# PowerMeterShield.net
KiCad netlist of a schematic drawn in EAGLE
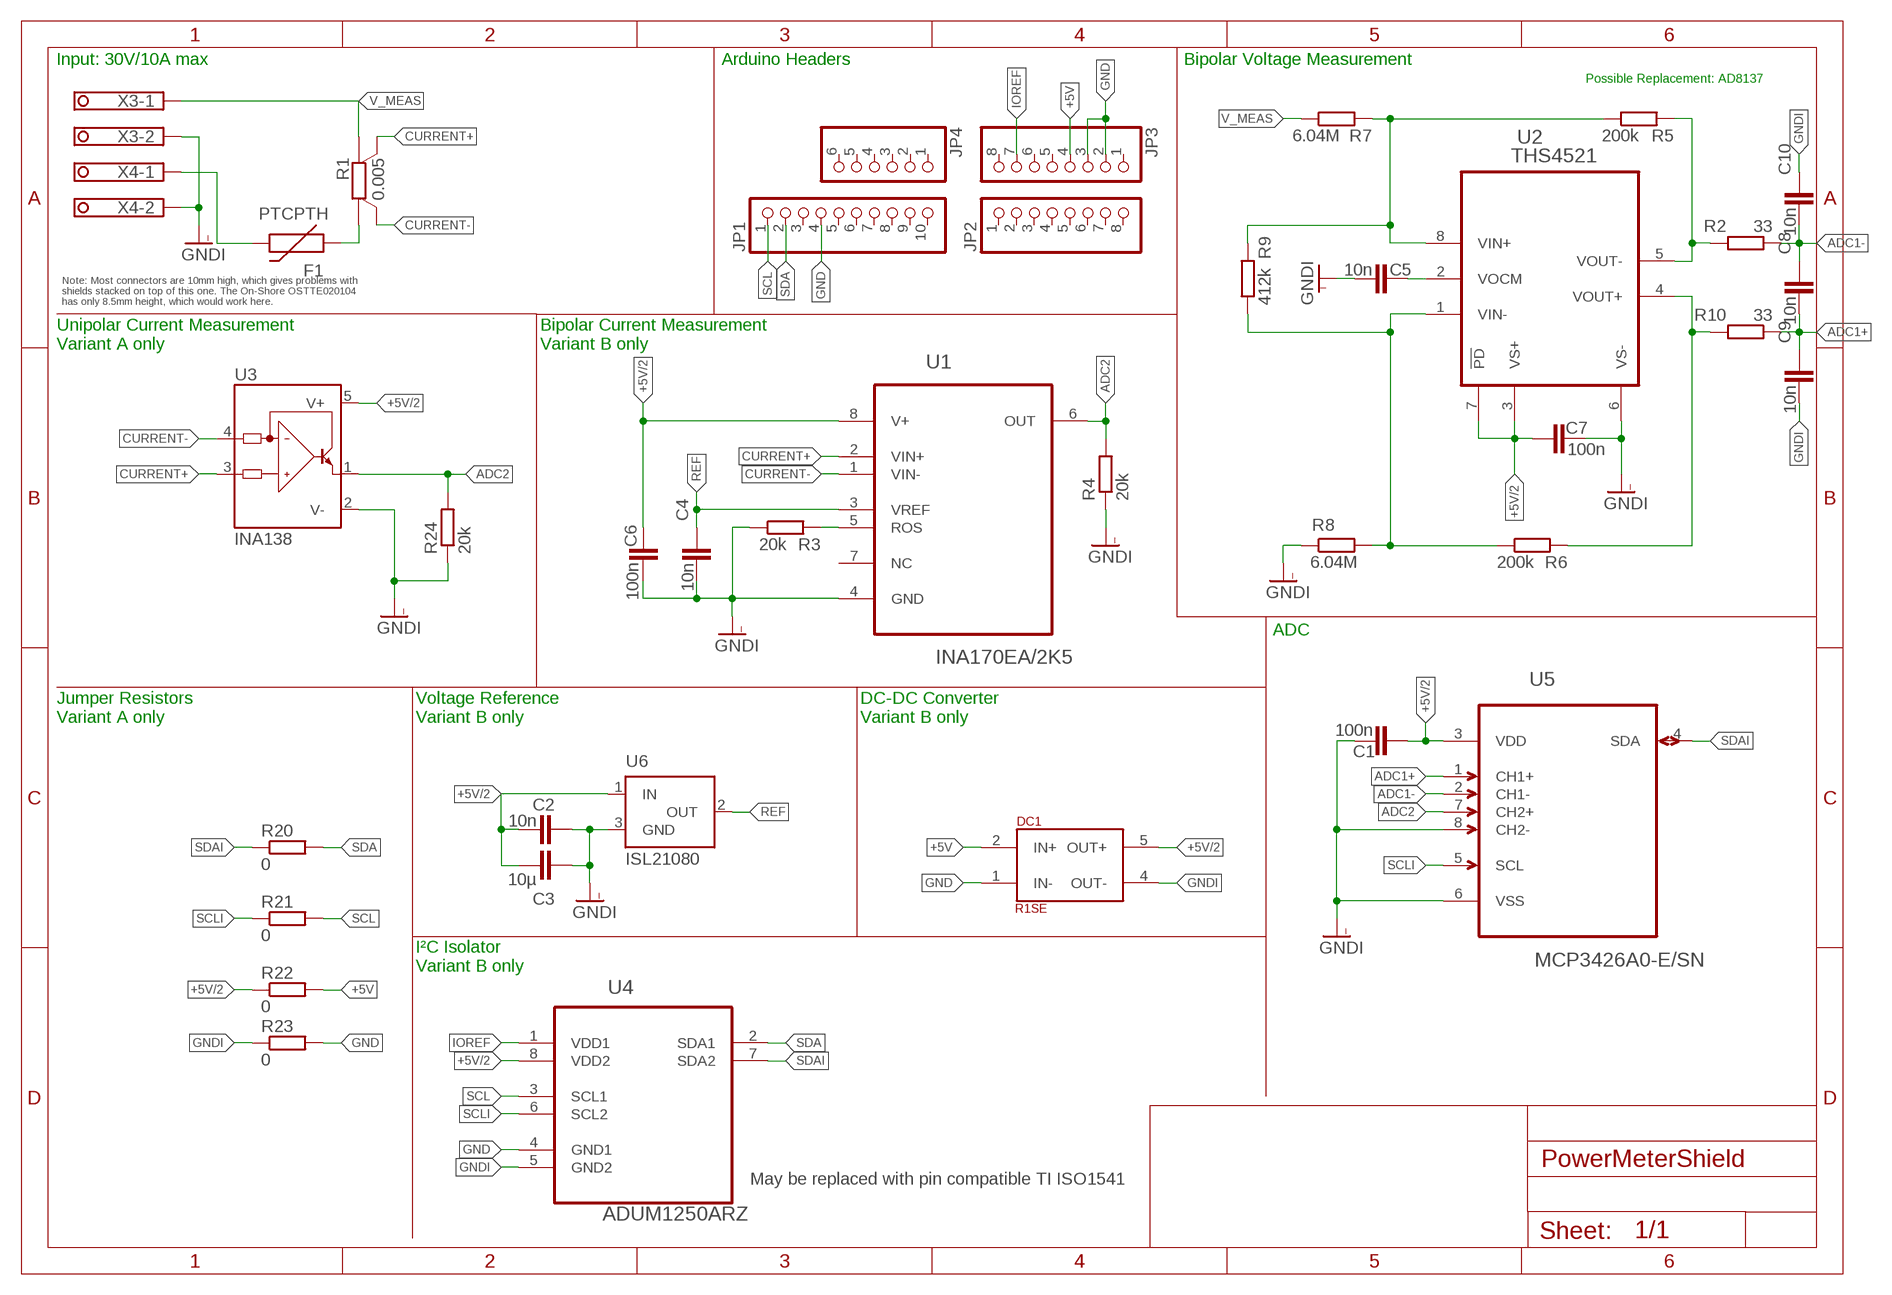
[diagram p0: schematic, sheet 1]

(export (version "E")
  (design (tool "Eeschema 10.0.6"))
  (components
    (comp (ref "C1")
      (value "100n")
      (footprint "eagle-import:C0805")
      (libsource (lib "eagle-import") (part "C-EUC0805"))
    )
    (comp (ref "C2")
      (value "10n")
      (footprint "eagle-import:C0805")
      (libsource (lib "eagle-import") (part "C-EUC0805"))
    )
    (comp (ref "C3")
      (value "10µ")
      (footprint "eagle-import:C0805")
      (libsource (lib "eagle-import") (part "C-EUC0805"))
    )
    (comp (ref "C4")
      (value "10n")
      (footprint "eagle-import:C0805")
      (libsource (lib "eagle-import") (part "C-EUC0805"))
    )
    (comp (ref "C5")
      (value "10n")
      (footprint "eagle-import:C0805")
      (libsource (lib "eagle-import") (part "C-EUC0805"))
    )
    (comp (ref "C6")
      (value "100n")
      (footprint "eagle-import:C0805")
      (libsource (lib "eagle-import") (part "C-EUC0805"))
    )
    (comp (ref "C7")
      (value "100n")
      (footprint "eagle-import:C0805")
      (libsource (lib "eagle-import") (part "C-EUC0805"))
    )
    (comp (ref "C8")
      (value "10n")
      (footprint "eagle-import:C0805")
      (libsource (lib "eagle-import") (part "C-EUC0805"))
    )
    (comp (ref "C9")
      (value "10n")
      (footprint "eagle-import:C0805")
      (libsource (lib "eagle-import") (part "C-EUC0805"))
    )
    (comp (ref "C10")
      (value "10n")
      (footprint "eagle-import:C0805")
      (libsource (lib "eagle-import") (part "C-EUC0805"))
    )
    (comp (ref "DC1")
      (value "R1SE")
      (footprint "eagle-import:R1SE")
      (libsource (lib "eagle-import") (part "R1SE"))
    )
    (comp (ref "F1")
      (value "PTCPTH")
      (footprint "eagle-import:PTC")
      (libsource (lib "eagle-import") (part "PTCPTH"))
    )
    (comp (ref "JP1")
      (value "PINHD-1X10")
      (footprint "eagle-import:1X10")
      (libsource (lib "eagle-import") (part "PINHD-1X10"))
    )
    (comp (ref "JP2")
      (value "PINHD-1X8")
      (footprint "eagle-import:1X08")
      (libsource (lib "eagle-import") (part "PINHD-1X8"))
    )
    (comp (ref "JP3")
      (value "PINHD-1X8")
      (footprint "eagle-import:1X08")
      (libsource (lib "eagle-import") (part "PINHD-1X8"))
    )
    (comp (ref "JP4")
      (value "PINHD-1X6")
      (footprint "eagle-import:1X06")
      (libsource (lib "eagle-import") (part "PINHD-1X6"))
    )
    (comp (ref "R1")
      (value "0.005")
      (footprint "eagle-import:CSM3637M")
      (libsource (lib "eagle-import") (part "SHUNT-4CSM3675M"))
    )
    (comp (ref "R2")
      (value "33")
      (footprint "eagle-import:R0805")
      (libsource (lib "eagle-import") (part "R-EU_R0805"))
    )
    (comp (ref "R3")
      (value "20k")
      (footprint "eagle-import:R0805")
      (libsource (lib "eagle-import") (part "R-EU_R0805"))
    )
    (comp (ref "R4")
      (value "20k")
      (footprint "eagle-import:R0805")
      (libsource (lib "eagle-import") (part "R-EU_R0805"))
    )
    (comp (ref "R5")
      (value "200k")
      (footprint "eagle-import:R0805")
      (libsource (lib "eagle-import") (part "R-EU_R0805"))
    )
    (comp (ref "R6")
      (value "200k")
      (footprint "eagle-import:R0805")
      (libsource (lib "eagle-import") (part "R-EU_R0805"))
    )
    (comp (ref "R7")
      (value "6.04M")
      (footprint "eagle-import:R0805")
      (libsource (lib "eagle-import") (part "R-EU_R0805"))
    )
    (comp (ref "R8")
      (value "6.04M")
      (footprint "eagle-import:R0805")
      (libsource (lib "eagle-import") (part "R-EU_R0805"))
    )
    (comp (ref "R9")
      (value "412k")
      (footprint "eagle-import:R0805")
      (libsource (lib "eagle-import") (part "R-EU_R0805"))
    )
    (comp (ref "R10")
      (value "33")
      (footprint "eagle-import:R0805")
      (libsource (lib "eagle-import") (part "R-EU_R0805"))
    )
    (comp (ref "R20")
      (value "0")
      (footprint "eagle-import:R2010")
      (libsource (lib "eagle-import") (part "R-EU_R2010"))
    )
    (comp (ref "R21")
      (value "0")
      (footprint "eagle-import:R2010")
      (libsource (lib "eagle-import") (part "R-EU_R2010"))
    )
    (comp (ref "R22")
      (value "0")
      (footprint "eagle-import:R2010")
      (libsource (lib "eagle-import") (part "R-EU_R2010"))
    )
    (comp (ref "R23")
      (value "0")
      (footprint "eagle-import:R2010")
      (libsource (lib "eagle-import") (part "R-EU_R2010"))
    )
    (comp (ref "R24")
      (value "20k")
      (footprint "eagle-import:R0805")
      (libsource (lib "eagle-import") (part "R-EU_R0805"))
    )
    (comp (ref "U1")
      (value "INA170EA/2K5")
      (footprint "eagle-import:SOP65P490X110-8N")
      (fields (field (name "OC_FARNELL") "1234851"))
      (libsource (lib "eagle-import") (part "INA170EA/2K5"))
    )
    (comp (ref "U2")
      (value "THS4521")
      (footprint "eagle-import:SOIC127P600X175-8N")
      (fields (field (name "MPN") "THS4531AID") (field (name "OC_FARNELL") "1755708"))
      (libsource (lib "eagle-import") (part "THS4531AID"))
    )
    (comp (ref "U3")
      (value "INA138")
      (footprint "eagle-import:SOT23-5")
      (fields (field (name "MF") "TEXAS INSTRUMENTS") (field (name "MPN") "INA138NA/250"))
      (libsource (lib "eagle-import") (part "INA138"))
    )
    (comp (ref "U4")
      (value "ADUM1250ARZ")
      (footprint "eagle-import:SOIC127P600X175-8N")
      (libsource (lib "eagle-import") (part "ADUM1250ARZ"))
    )
    (comp (ref "U5")
      (value "MCP3426A0-E/SN")
      (footprint "eagle-import:SOIC127P600X175-8N")
      (libsource (lib "eagle-import") (part "MCP3426A0-E/SN"))
    )
    (comp (ref "U6")
      (value "ISL21080")
      (footprint "eagle-import:SOT23")
      (fields (field (name "MF") "MAXIM") (field (name "MPN") "MAX6520EUR-T"))
      (libsource (lib "eagle-import") (part "MAX6520"))
    )
    (comp (ref "X3")
      (value "1751248")
      (footprint "eagle-import:1751248")
      (fields
        (field (name "OC_DIGIKEY") "ED2740-ND")
        (field (name "PRICE_10") "0.27")
        (field (name "PRICE_100") "0.19")
      )
      (libsource (lib "eagle-import") (part "1751248"))
    )
    (comp (ref "X4")
      (value "1751248")
      (footprint "eagle-import:1751248")
      (fields
        (field (name "OC_DIGIKEY") "ED2740-ND")
        (field (name "PRICE_10") "0.27")
        (field (name "PRICE_100") "0.19")
      )
      (libsource (lib "eagle-import") (part "1751248"))
    )
  )
  (nets
    (net (code "1") (name "+5V") (class "Default")
      (node (ref "DC1") (pin "2") (pinfunction "IN+_2") (pintype "bidirectional"))
      (node (ref "JP3") (pin "4") (pinfunction "4_4") (pintype "passive"))
      (node (ref "R22") (pin "2") (pinfunction "2_2") (pintype "passive"))
    )
    (net (code "2") (name "+5V{slash}2") (class "Default")
      (node (ref "C1") (pin "1") (pinfunction "1_1") (pintype "passive"))
      (node (ref "C2") (pin "1") (pinfunction "1_1") (pintype "passive"))
      (node (ref "C3") (pin "1") (pinfunction "1_1") (pintype "passive"))
      (node (ref "C6") (pin "1") (pinfunction "1_1") (pintype "passive"))
      (node (ref "C7") (pin "1") (pinfunction "1_1") (pintype "passive"))
      (node (ref "DC1") (pin "5") (pinfunction "OUT+_5") (pintype "bidirectional"))
      (node (ref "R22") (pin "1") (pinfunction "1_1") (pintype "passive"))
      (node (ref "U1") (pin "8") (pinfunction "V+_8") (pintype "power_in"))
      (node (ref "U2") (pin "3") (pinfunction "VS+_3") (pintype "input"))
      (node (ref "U2") (pin "7") (pinfunction "~{PD}_7") (pintype "power_in"))
      (node (ref "U3") (pin "5") (pinfunction "V+_5") (pintype "power_in"))
      (node (ref "U4") (pin "8") (pinfunction "VDD2_8") (pintype "power_in"))
      (node (ref "U5") (pin "3") (pinfunction "VDD_3") (pintype "power_in"))
      (node (ref "U6") (pin "1") (pinfunction "IN_1") (pintype "input"))
    )
    (net (code "3") (name "ADC1+") (class "Default")
      (node (ref "C8") (pin "1") (pinfunction "1_1") (pintype "passive"))
      (node (ref "C9") (pin "2") (pinfunction "2_2") (pintype "passive"))
      (node (ref "R10") (pin "1") (pinfunction "1_1") (pintype "passive"))
      (node (ref "U5") (pin "1") (pinfunction "CH1+_1") (pintype "input"))
    )
    (net (code "4") (name "ADC1-") (class "Default")
      (node (ref "C10") (pin "1") (pinfunction "1_1") (pintype "passive"))
      (node (ref "C8") (pin "2") (pinfunction "2_2") (pintype "passive"))
      (node (ref "R2") (pin "1") (pinfunction "1_1") (pintype "passive"))
      (node (ref "U5") (pin "2") (pinfunction "CH1-_2") (pintype "input"))
    )
    (net (code "5") (name "ADC2") (class "Default")
      (node (ref "R24") (pin "2") (pinfunction "2_2") (pintype "passive"))
      (node (ref "R4") (pin "2") (pinfunction "2_2") (pintype "passive"))
      (node (ref "U1") (pin "6") (pinfunction "OUT_6") (pintype "output"))
      (node (ref "U3") (pin "1") (pinfunction "OUT_1") (pintype "output"))
      (node (ref "U5") (pin "7") (pinfunction "CH2+_7") (pintype "input"))
    )
    (net (code "6") (name "CURRENT+") (class "Default")
      (node (ref "R1") (pin "S2") (pinfunction "S2_S2") (pintype "passive"))
      (node (ref "U1") (pin "2") (pinfunction "VIN+_2") (pintype "input"))
      (node (ref "U3") (pin "3") (pinfunction "IN+_3") (pintype "input"))
    )
    (net (code "7") (name "CURRENT-") (class "Default")
      (node (ref "R1") (pin "S1") (pinfunction "S1_S1") (pintype "passive"))
      (node (ref "U1") (pin "1") (pinfunction "VIN-_1") (pintype "input"))
      (node (ref "U3") (pin "4") (pinfunction "IN-_4") (pintype "input"))
    )
    (net (code "8") (name "GND") (class "Default")
      (node (ref "DC1") (pin "1") (pinfunction "IN-_1") (pintype "bidirectional"))
      (node (ref "JP1") (pin "4") (pinfunction "4_4") (pintype "passive"))
      (node (ref "JP3") (pin "2") (pinfunction "2_2") (pintype "passive"))
      (node (ref "JP3") (pin "3") (pinfunction "3_3") (pintype "passive"))
      (node (ref "R23") (pin "2") (pinfunction "2_2") (pintype "passive"))
      (node (ref "U4") (pin "4") (pinfunction "GND1_4") (pintype "passive"))
    )
    (net (code "9") (name "GNDI") (class "Default")
      (node (ref "C1") (pin "2") (pinfunction "2_2") (pintype "passive"))
      (node (ref "C10") (pin "2") (pinfunction "2_2") (pintype "passive"))
      (node (ref "C2") (pin "2") (pinfunction "2_2") (pintype "passive"))
      (node (ref "C3") (pin "2") (pinfunction "2_2") (pintype "passive"))
      (node (ref "C4") (pin "1") (pinfunction "1_1") (pintype "passive"))
      (node (ref "C5") (pin "1") (pinfunction "1_1") (pintype "passive"))
      (node (ref "C6") (pin "2") (pinfunction "2_2") (pintype "passive"))
      (node (ref "C7") (pin "2") (pinfunction "2_2") (pintype "passive"))
      (node (ref "C9") (pin "1") (pinfunction "1_1") (pintype "passive"))
      (node (ref "DC1") (pin "4") (pinfunction "OUT-_4") (pintype "bidirectional"))
      (node (ref "R23") (pin "1") (pinfunction "1_1") (pintype "passive"))
      (node (ref "R24") (pin "1") (pinfunction "1_1") (pintype "passive"))
      (node (ref "R3") (pin "1") (pinfunction "1_1") (pintype "passive"))
      (node (ref "R4") (pin "1") (pinfunction "1_1") (pintype "passive"))
      (node (ref "R8") (pin "1") (pinfunction "1_1") (pintype "passive"))
      (node (ref "U1") (pin "4") (pinfunction "GND_4") (pintype "passive"))
      (node (ref "U2") (pin "6") (pinfunction "VS-_6") (pintype "passive"))
      (node (ref "U3") (pin "2") (pinfunction "V-_2") (pintype "power_in"))
      (node (ref "U4") (pin "5") (pinfunction "GND2_5") (pintype "passive"))
      (node (ref "U5") (pin "6") (pinfunction "VSS_6") (pintype "power_in"))
      (node (ref "U5") (pin "8") (pinfunction "CH2-_8") (pintype "input"))
      (node (ref "U6") (pin "3") (pinfunction "GND_3") (pintype "power_in"))
      (node (ref "X3") (pin "2") (pinfunction "K_2") (pintype "passive"))
      (node (ref "X4") (pin "2") (pinfunction "K_2") (pintype "passive"))
    )
    (net (code "10") (name "IOREF") (class "Default")
      (node (ref "JP3") (pin "7") (pinfunction "7_7") (pintype "passive"))
      (node (ref "U4") (pin "1") (pinfunction "VDD1_1") (pintype "power_in"))
    )
    (net (code "11") (name "Net-(F1-1)") (class "Default")
      (node (ref "F1") (pin "P$1") (pinfunction "1_P$1") (pintype "bidirectional"))
      (node (ref "R1") (pin "I1") (pinfunction "I1_I1") (pintype "passive"))
    )
    (net (code "12") (name "Net-(F1-2)") (class "Default")
      (node (ref "F1") (pin "P$2") (pinfunction "2_P$2") (pintype "bidirectional"))
      (node (ref "X4") (pin "1") (pinfunction "K_1") (pintype "passive"))
    )
    (net (code "13") (name "Net-(U1-ROS)") (class "Default")
      (node (ref "R3") (pin "2") (pinfunction "2_2") (pintype "passive"))
      (node (ref "U1") (pin "5") (pinfunction "ROS_5") (pintype "input"))
    )
    (net (code "14") (name "Net-(U2-VIN+)") (class "Default")
      (node (ref "R5") (pin "1") (pinfunction "1_1") (pintype "passive"))
      (node (ref "R7") (pin "2") (pinfunction "2_2") (pintype "passive"))
      (node (ref "R9") (pin "2") (pinfunction "2_2") (pintype "passive"))
      (node (ref "U2") (pin "8") (pinfunction "VIN+_8") (pintype "input"))
    )
    (net (code "15") (name "Net-(U2-VIN-)") (class "Default")
      (node (ref "R6") (pin "1") (pinfunction "1_1") (pintype "passive"))
      (node (ref "R8") (pin "2") (pinfunction "2_2") (pintype "passive"))
      (node (ref "R9") (pin "1") (pinfunction "1_1") (pintype "passive"))
      (node (ref "U2") (pin "1") (pinfunction "VIN-_1") (pintype "passive"))
    )
    (net (code "16") (name "Net-(U2-VOCM)") (class "Default")
      (node (ref "C5") (pin "2") (pinfunction "2_2") (pintype "passive"))
      (node (ref "U2") (pin "2") (pinfunction "VOCM_2") (pintype "input"))
    )
    (net (code "17") (name "Net-(U2-VOUT+)") (class "Default")
      (node (ref "R10") (pin "2") (pinfunction "2_2") (pintype "passive"))
      (node (ref "R6") (pin "2") (pinfunction "2_2") (pintype "passive"))
      (node (ref "U2") (pin "4") (pinfunction "VOUT+_4") (pintype "output"))
    )
    (net (code "18") (name "Net-(U2-VOUT-)") (class "Default")
      (node (ref "R2") (pin "2") (pinfunction "2_2") (pintype "passive"))
      (node (ref "R5") (pin "2") (pinfunction "2_2") (pintype "passive"))
      (node (ref "U2") (pin "5") (pinfunction "VOUT-_5") (pintype "output"))
    )
    (net (code "19") (name "REF") (class "Default")
      (node (ref "C4") (pin "2") (pinfunction "2_2") (pintype "passive"))
      (node (ref "U1") (pin "3") (pinfunction "VREF_3") (pintype "input"))
      (node (ref "U6") (pin "2") (pinfunction "OUT_2") (pintype "output"))
    )
    (net (code "20") (name "SCL") (class "Default")
      (node (ref "JP1") (pin "1") (pinfunction "1_1") (pintype "passive"))
      (node (ref "R21") (pin "2") (pinfunction "2_2") (pintype "passive"))
      (node (ref "U4") (pin "3") (pinfunction "SCL1_3") (pintype "input"))
    )
    (net (code "21") (name "SCLI") (class "Default")
      (node (ref "R21") (pin "1") (pinfunction "1_1") (pintype "passive"))
      (node (ref "U4") (pin "6") (pinfunction "SCL2_6") (pintype "input"))
      (node (ref "U5") (pin "5") (pinfunction "SCL_5") (pintype "input"))
    )
    (net (code "22") (name "SDA") (class "Default")
      (node (ref "JP1") (pin "2") (pinfunction "2_2") (pintype "passive"))
      (node (ref "R20") (pin "2") (pinfunction "2_2") (pintype "passive"))
      (node (ref "U4") (pin "2") (pinfunction "SDA1_2") (pintype "bidirectional"))
    )
    (net (code "23") (name "SDAI") (class "Default")
      (node (ref "R20") (pin "1") (pinfunction "1_1") (pintype "passive"))
      (node (ref "U4") (pin "7") (pinfunction "SDA2_7") (pintype "bidirectional"))
      (node (ref "U5") (pin "4") (pinfunction "SDA_4") (pintype "bidirectional"))
    )
    (net (code "24") (name "V_MEAS") (class "Default")
      (node (ref "R1") (pin "I2") (pinfunction "I2_I2") (pintype "passive"))
      (node (ref "R7") (pin "1") (pinfunction "1_1") (pintype "passive"))
      (node (ref "X3") (pin "1") (pinfunction "K_1") (pintype "passive"))
    )
    (net (code "25") (name "unconnected-(JP1-Pad3)") (class "Default")
      (node (ref "JP1") (pin "3") (pinfunction "3_3") (pintype "passive"))
    )
    (net (code "26") (name "unconnected-(JP1-Pad5)") (class "Default")
      (node (ref "JP1") (pin "5") (pinfunction "5_5") (pintype "passive"))
    )
    (net (code "27") (name "unconnected-(JP1-Pad6)") (class "Default")
      (node (ref "JP1") (pin "6") (pinfunction "6_6") (pintype "passive"))
    )
    (net (code "28") (name "unconnected-(JP1-Pad7)") (class "Default")
      (node (ref "JP1") (pin "7") (pinfunction "7_7") (pintype "passive"))
    )
    (net (code "29") (name "unconnected-(JP1-Pad8)") (class "Default")
      (node (ref "JP1") (pin "8") (pinfunction "8_8") (pintype "passive"))
    )
    (net (code "30") (name "unconnected-(JP1-Pad9)") (class "Default")
      (node (ref "JP1") (pin "9") (pinfunction "9_9") (pintype "passive"))
    )
    (net (code "31") (name "unconnected-(JP1-Pad10)") (class "Default")
      (node (ref "JP1") (pin "10") (pinfunction "10_10") (pintype "passive"))
    )
    (net (code "32") (name "unconnected-(JP2-Pad1)") (class "Default")
      (node (ref "JP2") (pin "1") (pinfunction "1_1") (pintype "passive"))
    )
    (net (code "33") (name "unconnected-(JP2-Pad2)") (class "Default")
      (node (ref "JP2") (pin "2") (pinfunction "2_2") (pintype "passive"))
    )
    (net (code "34") (name "unconnected-(JP2-Pad3)") (class "Default")
      (node (ref "JP2") (pin "3") (pinfunction "3_3") (pintype "passive"))
    )
    (net (code "35") (name "unconnected-(JP2-Pad4)") (class "Default")
      (node (ref "JP2") (pin "4") (pinfunction "4_4") (pintype "passive"))
    )
    (net (code "36") (name "unconnected-(JP2-Pad5)") (class "Default")
      (node (ref "JP2") (pin "5") (pinfunction "5_5") (pintype "passive"))
    )
    (net (code "37") (name "unconnected-(JP2-Pad6)") (class "Default")
      (node (ref "JP2") (pin "6") (pinfunction "6_6") (pintype "passive"))
    )
    (net (code "38") (name "unconnected-(JP2-Pad7)") (class "Default")
      (node (ref "JP2") (pin "7") (pinfunction "7_7") (pintype "passive"))
    )
    (net (code "39") (name "unconnected-(JP2-Pad8)") (class "Default")
      (node (ref "JP2") (pin "8") (pinfunction "8_8") (pintype "passive"))
    )
    (net (code "40") (name "unconnected-(JP3-Pad1)") (class "Default")
      (node (ref "JP3") (pin "1") (pinfunction "1_1") (pintype "passive"))
    )
    (net (code "41") (name "unconnected-(JP3-Pad5)") (class "Default")
      (node (ref "JP3") (pin "5") (pinfunction "5_5") (pintype "passive"))
    )
    (net (code "42") (name "unconnected-(JP3-Pad6)") (class "Default")
      (node (ref "JP3") (pin "6") (pinfunction "6_6") (pintype "passive"))
    )
    (net (code "43") (name "unconnected-(JP3-Pad8)") (class "Default")
      (node (ref "JP3") (pin "8") (pinfunction "8_8") (pintype "passive"))
    )
    (net (code "44") (name "unconnected-(JP4-Pad1)") (class "Default")
      (node (ref "JP4") (pin "1") (pinfunction "1_1") (pintype "passive"))
    )
    (net (code "45") (name "unconnected-(JP4-Pad2)") (class "Default")
      (node (ref "JP4") (pin "2") (pinfunction "2_2") (pintype "passive"))
    )
    (net (code "46") (name "unconnected-(JP4-Pad3)") (class "Default")
      (node (ref "JP4") (pin "3") (pinfunction "3_3") (pintype "passive"))
    )
    (net (code "47") (name "unconnected-(JP4-Pad4)") (class "Default")
      (node (ref "JP4") (pin "4") (pinfunction "4_4") (pintype "passive"))
    )
    (net (code "48") (name "unconnected-(JP4-Pad5)") (class "Default")
      (node (ref "JP4") (pin "5") (pinfunction "5_5") (pintype "passive"))
    )
    (net (code "49") (name "unconnected-(JP4-Pad6)") (class "Default")
      (node (ref "JP4") (pin "6") (pinfunction "6_6") (pintype "passive"))
    )
    (net (code "50") (name "unconnected-(U1-NC-Pad7)") (class "Default")
      (node (ref "U1") (pin "7") (pinfunction "NC_7") (pintype "no_connect"))
    )
  )
)
